# rough.net
KiCad netlist of a schematic drawn in EAGLE
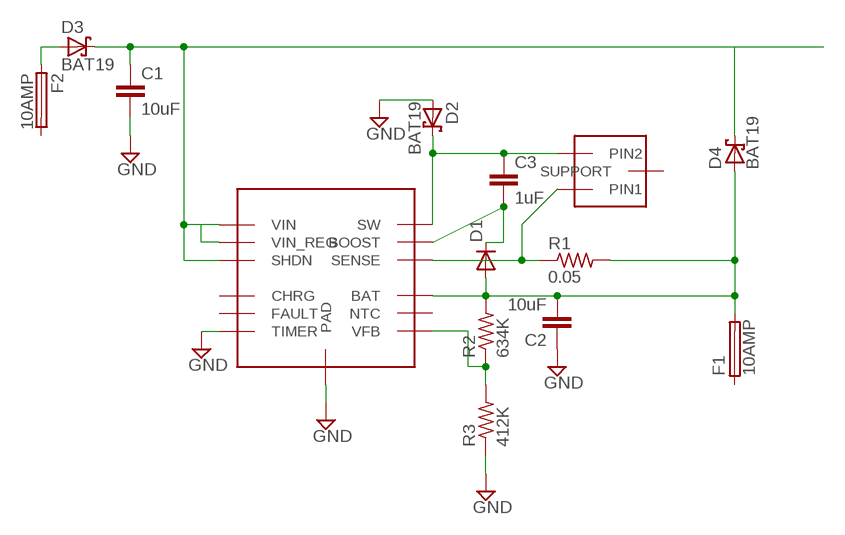
[diagram p0: schematic, sheet 1]

(export (version "E")
  (design (tool "Eeschema 10.0.6"))
  (components
    (comp (ref "C1")
      (value "10uF")
      (footprint "eagle-import:C5B3.5")
      (libsource (lib "eagle-import") (part "C5/3.5"))
    )
    (comp (ref "C2")
      (value "10uF")
      (footprint "eagle-import:C5B3.5")
      (libsource (lib "eagle-import") (part "C5/3.5"))
    )
    (comp (ref "C3")
      (value "1uF")
      (footprint "eagle-import:C5B3.5")
      (libsource (lib "eagle-import") (part "C5/3.5"))
    )
    (comp (ref "D1")
      (value "DIODE-SOD80C")
      (footprint "eagle-import:SOD80C")
      (libsource (lib "eagle-import") (part "DIODE-SOD80C"))
    )
    (comp (ref "D2")
      (value "BAT19")
      (footprint "eagle-import:DO35-10")
      (libsource (lib "eagle-import") (part "BAT19"))
    )
    (comp (ref "D3")
      (value "BAT19")
      (footprint "eagle-import:DO35-10")
      (libsource (lib "eagle-import") (part "BAT19"))
    )
    (comp (ref "D4")
      (value "BAT19")
      (footprint "eagle-import:DO35-10")
      (libsource (lib "eagle-import") (part "BAT19"))
    )
    (comp (ref "F1")
      (value "10AMP")
      (footprint "eagle-import:SH22,5")
      (fields (field (name "MF") "SCHURTER") (field (name "MPN") "0031.8201"))
      (libsource (lib "eagle-import") (part "SH22,5"))
    )
    (comp (ref "F2")
      (value "10AMP")
      (footprint "eagle-import:SH22,5")
      (fields (field (name "MF") "SCHURTER") (field (name "MPN") "0031.8201"))
      (libsource (lib "eagle-import") (part "SH22,5"))
    )
    (comp (ref "INDUCTOR")
      (value "INDUCTOR")
      (footprint "eagle-import:3LEADINDUCTOR")
      (libsource (lib "eagle-import") (part "INDUCTOR"))
    )
    (comp (ref "R1")
      (value "0.05")
      (footprint "eagle-import:R1206")
      (libsource (lib "eagle-import") (part "resistor_R-US_R1206"))
    )
    (comp (ref "R2")
      (value "634K")
      (footprint "eagle-import:M2012")
      (libsource (lib "eagle-import") (part "R-US_M2012"))
    )
    (comp (ref "R3")
      (value "412K")
      (footprint "eagle-import:M2012")
      (libsource (lib "eagle-import") (part "R-US_M2012"))
    )
    (comp (ref "U$1")
      (value "LT3652")
      (footprint "eagle-import:DD-12-LEAD-3MMX3MM")
      (libsource (lib "eagle-import") (part "LT3652"))
    )
  )
  (nets
    (net (code "1") (name "GND") (class "Default")
      (node (ref "C1") (pin "2") (pinfunction "2_2") (pintype "passive"))
      (node (ref "C2") (pin "1") (pinfunction "1_1") (pintype "passive"))
      (node (ref "D2") (pin "A") (pinfunction "A_A") (pintype "passive"))
      (node (ref "R3") (pin "1") (pinfunction "1_1") (pintype "passive"))
      (node (ref "U$1") (pin "P$1") (pinfunction "PAD_P$1") (pintype "bidirectional"))
      (node (ref "U$1") (pin "TIMER") (pinfunction "TIMER_TIMER") (pintype "bidirectional"))
    )
    (net (code "2") (name "Net-(C2-Pad2)") (class "Default")
      (node (ref "C2") (pin "2") (pinfunction "2_2") (pintype "passive"))
      (node (ref "D1") (pin "A") (pinfunction "A_A") (pintype "passive"))
      (node (ref "D4") (pin "A") (pinfunction "A_A") (pintype "passive"))
      (node (ref "F1") (pin "2") (pinfunction "2_2") (pintype "passive"))
      (node (ref "R1") (pin "2") (pinfunction "2_2") (pintype "passive"))
      (node (ref "R2") (pin "2") (pinfunction "2_2") (pintype "passive"))
      (node (ref "U$1") (pin "BAT") (pinfunction "BAT_BAT") (pintype "bidirectional"))
    )
    (net (code "3") (name "Net-(C3-Pad1)") (class "Default")
      (node (ref "C3") (pin "1") (pinfunction "1_1") (pintype "passive"))
      (node (ref "D2") (pin "C") (pinfunction "C_C") (pintype "passive"))
      (node (ref "INDUCTOR") (pin "PIN2") (pinfunction "PIN2_PIN2") (pintype "bidirectional"))
      (node (ref "U$1") (pin "SW") (pinfunction "SW_SW") (pintype "bidirectional"))
    )
    (net (code "4") (name "Net-(C3-Pad2)") (class "Default")
      (node (ref "C3") (pin "2") (pinfunction "2_2") (pintype "passive"))
      (node (ref "D1") (pin "C") (pinfunction "C_C") (pintype "passive"))
      (node (ref "U$1") (pin "BOOST") (pinfunction "BOOST_BOOST") (pintype "bidirectional"))
    )
    (net (code "5") (name "Net-(D3-PadA)") (class "Default")
      (node (ref "D3") (pin "A") (pinfunction "A_A") (pintype "passive"))
      (node (ref "F2") (pin "1") (pinfunction "1_1") (pintype "passive"))
    )
    (net (code "6") (name "Net-(INDUCTOR-PadPIN1)") (class "Default")
      (node (ref "INDUCTOR") (pin "PIN1") (pinfunction "PIN1_PIN1") (pintype "bidirectional"))
      (node (ref "R1") (pin "1") (pinfunction "1_1") (pintype "passive"))
      (node (ref "U$1") (pin "SENSE") (pinfunction "SENSE_SENSE") (pintype "bidirectional"))
    )
    (net (code "7") (name "Net-(R2-Pad1)") (class "Default")
      (node (ref "R2") (pin "1") (pinfunction "1_1") (pintype "passive"))
      (node (ref "R3") (pin "2") (pinfunction "2_2") (pintype "passive"))
      (node (ref "U$1") (pin "VFB") (pinfunction "VFB_VFB") (pintype "bidirectional"))
    )
    (net (code "8") (name "Net-(U$1-VIN)") (class "Default")
      (node (ref "C1") (pin "1") (pinfunction "1_1") (pintype "passive"))
      (node (ref "D3") (pin "C") (pinfunction "C_C") (pintype "passive"))
      (node (ref "D4") (pin "C") (pinfunction "C_C") (pintype "passive"))
      (node (ref "U$1") (pin "SHDN") (pinfunction "SHDN_SHDN") (pintype "bidirectional"))
      (node (ref "U$1") (pin "VIN_REG") (pinfunction "VIN_REG_VIN_REG") (pintype "bidirectional"))
      (node (ref "U$1") (pin "V_IN") (pinfunction "VIN_V_IN") (pintype "bidirectional"))
    )
    (net (code "9") (name "unconnected-(F1-Pad1)") (class "Default")
      (node (ref "F1") (pin "1") (pinfunction "1_1") (pintype "passive"))
    )
    (net (code "10") (name "unconnected-(F2-Pad2)") (class "Default")
      (node (ref "F2") (pin "2") (pinfunction "2_2") (pintype "passive"))
    )
    (net (code "11") (name "unconnected-(INDUCTOR-PadSUPPORT)") (class "Default")
      (node (ref "INDUCTOR") (pin "SUPPORT") (pinfunction "SUPPORT_SUPPORT") (pintype "bidirectional"))
    )
    (net (code "12") (name "unconnected-(U$1-PadCHRG)") (class "Default")
      (node (ref "U$1") (pin "CHRG") (pinfunction "CHRG_CHRG") (pintype "bidirectional"))
    )
    (net (code "13") (name "unconnected-(U$1-PadFAULT)") (class "Default")
      (node (ref "U$1") (pin "FAULT") (pinfunction "FAULT_FAULT") (pintype "bidirectional"))
    )
    (net (code "14") (name "unconnected-(U$1-PadNTC)") (class "Default")
      (node (ref "U$1") (pin "NTC") (pinfunction "NTC_NTC") (pintype "bidirectional"))
    )
  )
)
